# rect_and_stab.net
KiCad netlist of a schematic drawn in EAGLE
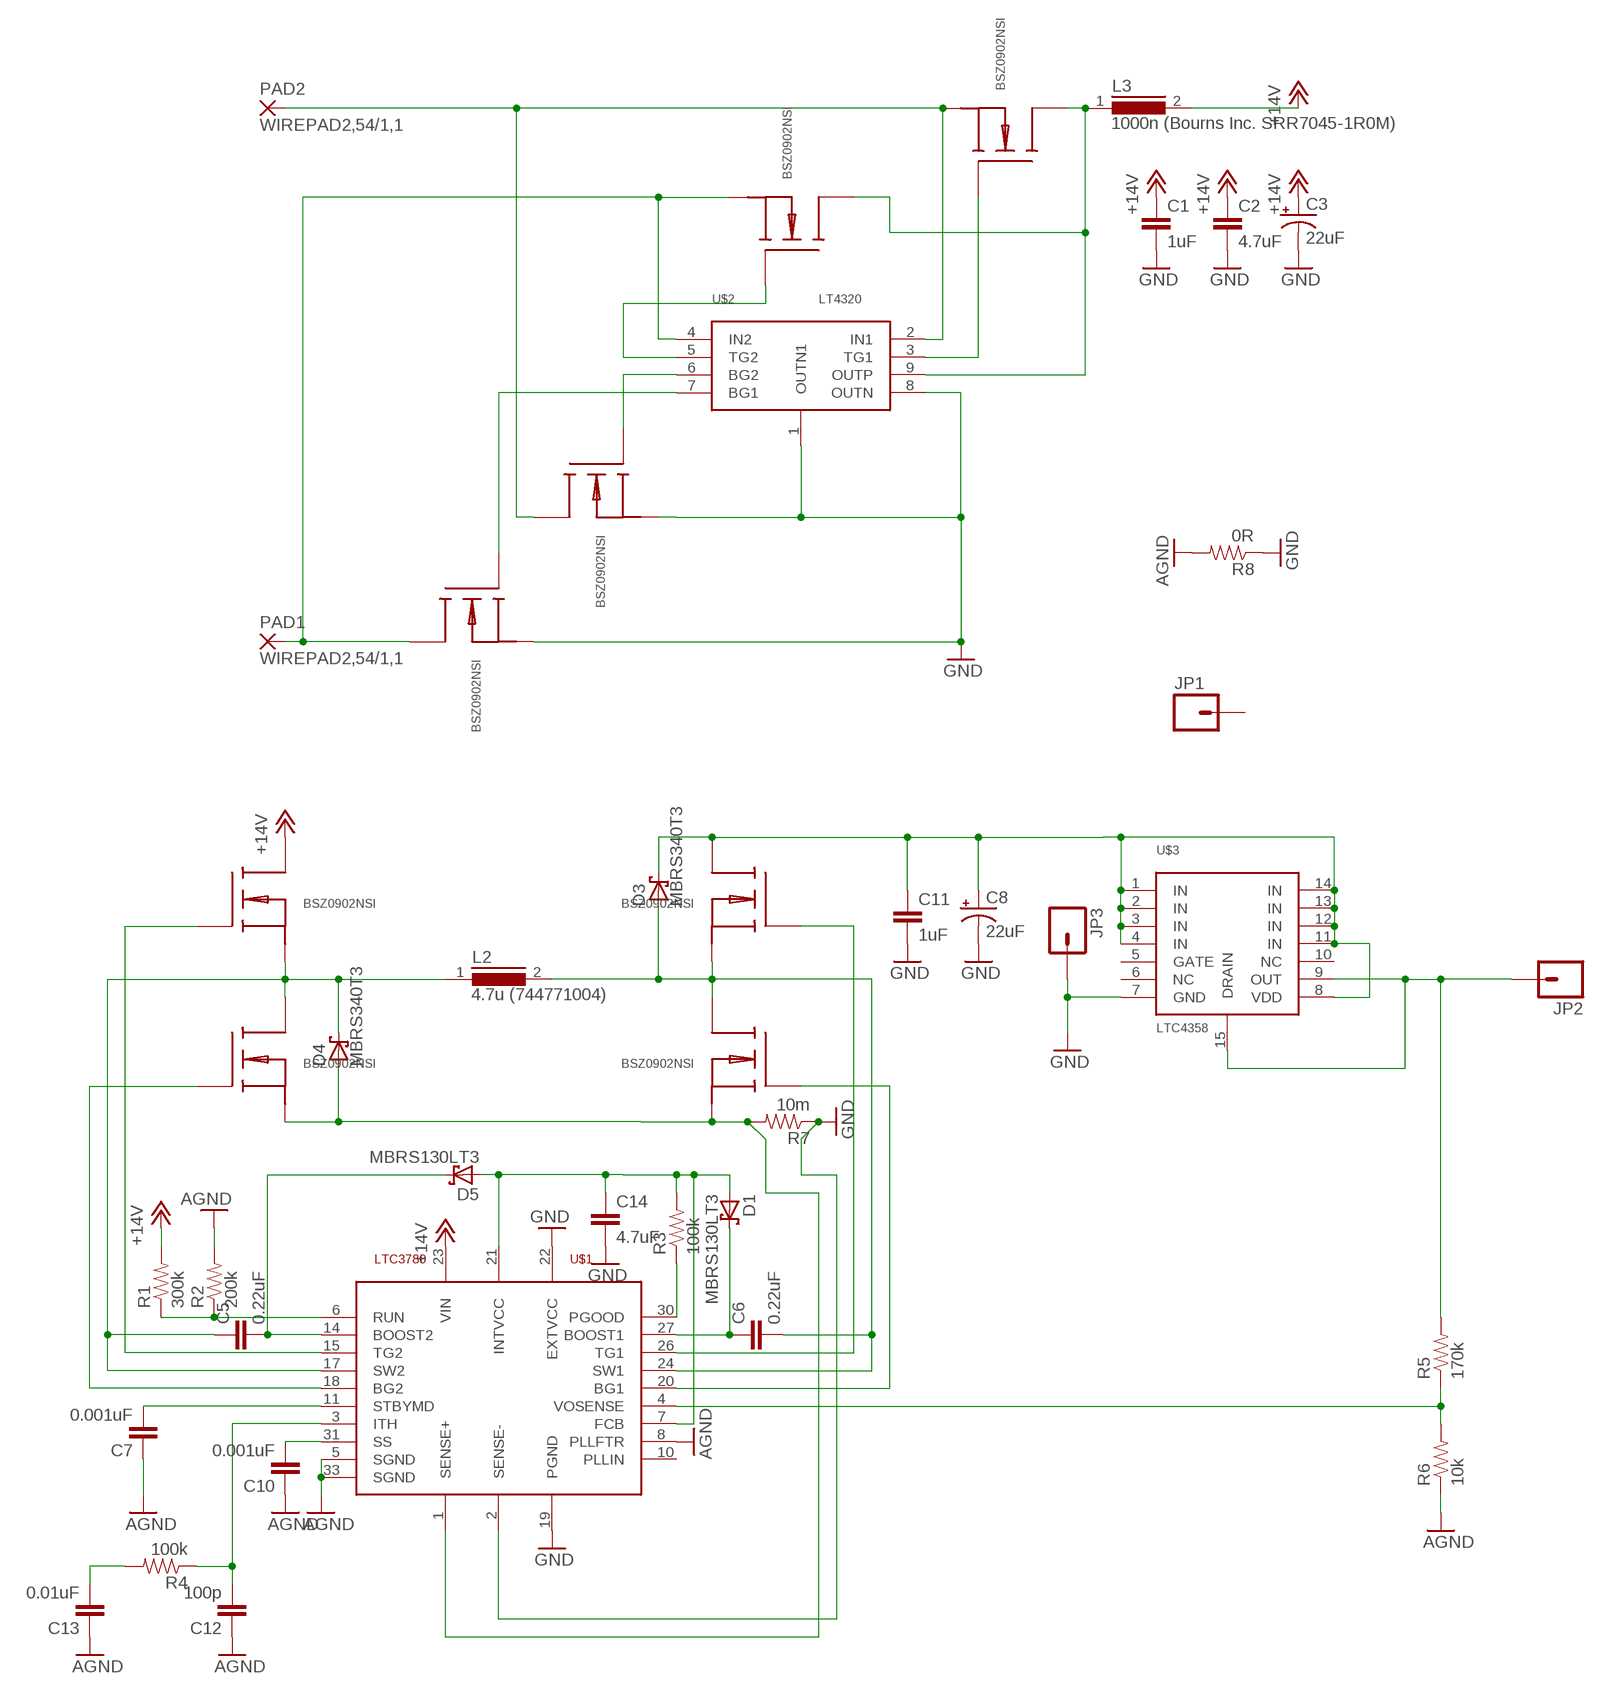
[diagram p0: schematic, sheet 1]

(export (version "E")
  (design (tool "Eeschema 10.0.6"))
  (components
    (comp (ref "C1")
      (value "1uF")
      (footprint "eagle-import:0603-CAP")
      (libsource (lib "eagle-import") (part "CAP0603-CAP"))
    )
    (comp (ref "C2")
      (value "4.7uF")
      (footprint "eagle-import:1210")
      (libsource (lib "eagle-import") (part "CAP1210"))
    )
    (comp (ref "C3")
      (value "22uF")
      (footprint "eagle-import:EIA7343")
      (libsource (lib "eagle-import") (part "CAP_POL7343"))
    )
    (comp (ref "C5")
      (value "0.22uF")
      (footprint "eagle-import:0603-CAP")
      (libsource (lib "eagle-import") (part "CAP0603-CAP"))
    )
    (comp (ref "C6")
      (value "0.22uF")
      (footprint "eagle-import:0603-CAP")
      (libsource (lib "eagle-import") (part "CAP0603-CAP"))
    )
    (comp (ref "C7")
      (value "0.001uF")
      (footprint "eagle-import:0402-CAP")
      (libsource (lib "eagle-import") (part "0.1UF-16V(+-10%)(0402)"))
    )
    (comp (ref "C8")
      (value "22uF")
      (footprint "eagle-import:EIA7343")
      (libsource (lib "eagle-import") (part "CAP_POL7343"))
    )
    (comp (ref "C10")
      (value "0.001uF")
      (footprint "eagle-import:0402-CAP")
      (libsource (lib "eagle-import") (part "0.1UF-16V(+-10%)(0402)"))
    )
    (comp (ref "C11")
      (value "1uF")
      (footprint "eagle-import:0603-CAP")
      (libsource (lib "eagle-import") (part "CAP0603-CAP"))
    )
    (comp (ref "C12")
      (value "100p")
      (footprint "eagle-import:0402-CAP")
      (libsource (lib "eagle-import") (part "0.1UF-16V(+-10%)(0402)"))
    )
    (comp (ref "C13")
      (value "0.01uF")
      (footprint "eagle-import:0402-CAP")
      (libsource (lib "eagle-import") (part "0.1UF-16V(+-10%)(0402)"))
    )
    (comp (ref "C14")
      (value "4.7uF")
      (footprint "eagle-import:1210")
      (libsource (lib "eagle-import") (part "CAP1210"))
    )
    (comp (ref "D1")
      (value "MBRS130LT3")
      (footprint "eagle-import:SMB")
      (libsource (lib "eagle-import") (part "MBRS130LT3"))
    )
    (comp (ref "D3")
      (value "MBRS340T3")
      (footprint "eagle-import:SMC")
      (libsource (lib "eagle-import") (part "MBRS30T34"))
    )
    (comp (ref "D4")
      (value "MBRS340T3")
      (footprint "eagle-import:SMC")
      (libsource (lib "eagle-import") (part "MBRS30T34"))
    )
    (comp (ref "D5")
      (value "MBRS130LT3")
      (footprint "eagle-import:SMB")
      (libsource (lib "eagle-import") (part "MBRS130LT3"))
    )
    (comp (ref "JP1")
      (value "M01PTH_2MM")
      (footprint "eagle-import:1X01_2MM")
      (libsource (lib "eagle-import") (part "M01PTH_2MM"))
    )
    (comp (ref "JP2")
      (value "M01PTH_2MM")
      (footprint "eagle-import:1X01_2MM")
      (libsource (lib "eagle-import") (part "M01PTH_2MM"))
    )
    (comp (ref "JP3")
      (value "M01PTH_2MM")
      (footprint "eagle-import:1X01_2MM")
      (libsource (lib "eagle-import") (part "M01PTH_2MM"))
    )
    (comp (ref "L2")
      (value "4.7u (744771004)")
      (footprint "eagle-import:DR127")
      (libsource (lib "eagle-import") (part "DR127"))
    )
    (comp (ref "L3")
      (value "1000n (Bourns Inc. SRR7045-1R0M)")
      (footprint "eagle-import:DR74")
      (libsource (lib "eagle-import") (part "DR74"))
    )
    (comp (ref "PAD1")
      (value "WIREPAD2,54/1,1")
      (footprint "eagle-import:2,54_1,1")
      (libsource (lib "eagle-import") (part "WIREPAD2,54/1,1"))
    )
    (comp (ref "PAD2")
      (value "WIREPAD2,54/1,1")
      (footprint "eagle-import:2,54_1,1")
      (libsource (lib "eagle-import") (part "WIREPAD2,54/1,1"))
    )
    (comp (ref "Q1")
      (value "BSZ0902NSI")
      (footprint "eagle-import:BSZ090X")
      (libsource (lib "eagle-import") (part "BSZ090X"))
    )
    (comp (ref "Q2")
      (value "BSZ0902NSI")
      (footprint "eagle-import:BSZ090X")
      (libsource (lib "eagle-import") (part "BSZ090X"))
    )
    (comp (ref "Q3")
      (value "BSZ0902NSI")
      (footprint "eagle-import:BSZ090X")
      (libsource (lib "eagle-import") (part "BSZ090X"))
    )
    (comp (ref "Q4")
      (value "BSZ0902NSI")
      (footprint "eagle-import:BSZ090X")
      (libsource (lib "eagle-import") (part "BSZ090X"))
    )
    (comp (ref "Q5")
      (value "BSZ0902NSI")
      (footprint "eagle-import:BSZ090X")
      (libsource (lib "eagle-import") (part "BSZ090X"))
    )
    (comp (ref "Q6")
      (value "BSZ0902NSI")
      (footprint "eagle-import:BSZ090X")
      (libsource (lib "eagle-import") (part "BSZ090X"))
    )
    (comp (ref "Q7")
      (value "BSZ0902NSI")
      (footprint "eagle-import:BSZ090X")
      (libsource (lib "eagle-import") (part "BSZ090X"))
    )
    (comp (ref "Q8")
      (value "BSZ0902NSI")
      (footprint "eagle-import:BSZ090X")
      (libsource (lib "eagle-import") (part "BSZ090X"))
    )
    (comp (ref "R1")
      (value "300k")
      (footprint "eagle-import:0402-RES")
      (libsource (lib "eagle-import") (part "RESISTOR0402-RES"))
    )
    (comp (ref "R2")
      (value "200k")
      (footprint "eagle-import:0402-RES")
      (libsource (lib "eagle-import") (part "RESISTOR0402-RES"))
    )
    (comp (ref "R3")
      (value "100k")
      (footprint "eagle-import:0402-RES")
      (libsource (lib "eagle-import") (part "RESISTOR0402-RES"))
    )
    (comp (ref "R4")
      (value "100k")
      (footprint "eagle-import:0402-RES")
      (libsource (lib "eagle-import") (part "RESISTOR0402-RES"))
    )
    (comp (ref "R5")
      (value "170k")
      (footprint "eagle-import:0402-RES")
      (libsource (lib "eagle-import") (part "RESISTOR0402-RES"))
    )
    (comp (ref "R6")
      (value "10k")
      (footprint "eagle-import:0402-RES")
      (libsource (lib "eagle-import") (part "RESISTOR0402-RES"))
    )
    (comp (ref "R7")
      (value "10m")
      (footprint "eagle-import:R2010")
      (libsource (lib "eagle-import") (part "RESISTOR2010"))
    )
    (comp (ref "R8")
      (value "0R")
      (footprint "eagle-import:0402-RES")
      (libsource (lib "eagle-import") (part "RESISTOR0402-RES"))
    )
    (comp (ref "U$1")
      (value "LTC3780")
      (footprint "eagle-import:LTC3780")
      (libsource (lib "eagle-import") (part "LTC3780"))
    )
    (comp (ref "U$2")
      (value "LT4320")
      (footprint "eagle-import:LT4320")
      (libsource (lib "eagle-import") (part "LT4320"))
    )
    (comp (ref "U$3")
      (value "LTC4358")
      (footprint "eagle-import:LTC4358")
      (libsource (lib "eagle-import") (part "LTC4358"))
    )
  )
  (nets
    (net (code "1") (name "+14V") (class "Default")
      (node (ref "C1") (pin "1") (pinfunction "1_1") (pintype "passive"))
      (node (ref "C2") (pin "1") (pinfunction "1_1") (pintype "passive"))
      (node (ref "C3") (pin "A") (pinfunction "+_A") (pintype "passive"))
      (node (ref "L3") (pin "2") (pinfunction "2_2") (pintype "passive"))
      (node (ref "Q6") (pin "D") (pinfunction "D_D") (pintype "bidirectional"))
      (node (ref "Q6") (pin "D@1") (pinfunction "D_D@1") (pintype "bidirectional"))
      (node (ref "Q6") (pin "D@2") (pinfunction "D_D@2") (pintype "bidirectional"))
      (node (ref "Q6") (pin "D@3") (pinfunction "D_D@3") (pintype "bidirectional"))
      (node (ref "Q6") (pin "D@4") (pinfunction "D_D@4") (pintype "bidirectional"))
      (node (ref "R1") (pin "2") (pinfunction "2_2") (pintype "passive"))
      (node (ref "U$1") (pin "23") (pinfunction "VIN_23") (pintype "power_in"))
    )
    (net (code "2") (name "AGND") (class "Default")
      (node (ref "C10") (pin "1") (pinfunction "1_1") (pintype "passive"))
      (node (ref "C12") (pin "1") (pinfunction "1_1") (pintype "passive"))
      (node (ref "C13") (pin "1") (pinfunction "1_1") (pintype "passive"))
      (node (ref "C7") (pin "1") (pinfunction "1_1") (pintype "passive"))
      (node (ref "R2") (pin "2") (pinfunction "2_2") (pintype "passive"))
      (node (ref "R6") (pin "1") (pinfunction "1_1") (pintype "passive"))
      (node (ref "R8") (pin "2") (pinfunction "2_2") (pintype "passive"))
      (node (ref "U$1") (pin "33") (pinfunction "SGND_33") (pintype "power_in"))
      (node (ref "U$1") (pin "5") (pinfunction "SGND_5") (pintype "power_in"))
      (node (ref "U$1") (pin "8") (pinfunction "PLLFTR_8") (pintype "bidirectional"))
    )
    (net (code "3") (name "GND") (class "Default")
      (node (ref "C1") (pin "2") (pinfunction "2_2") (pintype "passive"))
      (node (ref "C11") (pin "2") (pinfunction "2_2") (pintype "passive"))
      (node (ref "C14") (pin "2") (pinfunction "2_2") (pintype "passive"))
      (node (ref "C2") (pin "2") (pinfunction "2_2") (pintype "passive"))
      (node (ref "C3") (pin "C") (pinfunction "-_C") (pintype "passive"))
      (node (ref "C8") (pin "C") (pinfunction "-_C") (pintype "passive"))
      (node (ref "JP3") (pin "1") (pinfunction "1_1") (pintype "passive"))
      (node (ref "Q1") (pin "S@1") (pinfunction "S_S@1") (pintype "bidirectional"))
      (node (ref "Q1") (pin "S@2") (pinfunction "S_S@2") (pintype "bidirectional"))
      (node (ref "Q1") (pin "S@3") (pinfunction "S_S@3") (pintype "bidirectional"))
      (node (ref "Q1") (pin "S@4") (pinfunction "S_S@4") (pintype "bidirectional"))
      (node (ref "Q3") (pin "S@1") (pinfunction "S_S@1") (pintype "bidirectional"))
      (node (ref "Q3") (pin "S@2") (pinfunction "S_S@2") (pintype "bidirectional"))
      (node (ref "Q3") (pin "S@3") (pinfunction "S_S@3") (pintype "bidirectional"))
      (node (ref "Q3") (pin "S@4") (pinfunction "S_S@4") (pintype "bidirectional"))
      (node (ref "R7") (pin "1") (pinfunction "1_1") (pintype "passive"))
      (node (ref "R8") (pin "1") (pinfunction "1_1") (pintype "passive"))
      (node (ref "U$1") (pin "19") (pinfunction "PGND_19") (pintype "power_in"))
      (node (ref "U$1") (pin "2") (pinfunction "SENSE-_2") (pintype "bidirectional"))
      (node (ref "U$1") (pin "22") (pinfunction "EXTVCC_22") (pintype "bidirectional"))
      (node (ref "U$2") (pin "1") (pinfunction "OUTN1_1") (pintype "bidirectional"))
      (node (ref "U$2") (pin "8") (pinfunction "OUTN_8") (pintype "bidirectional"))
      (node (ref "U$3") (pin "7") (pinfunction "GND_7") (pintype "bidirectional"))
    )
    (net (code "4") (name "Net-(C8-+)") (class "Default")
      (node (ref "C11") (pin "1") (pinfunction "1_1") (pintype "passive"))
      (node (ref "C8") (pin "A") (pinfunction "+_A") (pintype "passive"))
      (node (ref "D3") (pin "C") (pinfunction "C_C") (pintype "passive"))
      (node (ref "Q8") (pin "D") (pinfunction "D_D") (pintype "bidirectional"))
      (node (ref "Q8") (pin "D@1") (pinfunction "D_D@1") (pintype "bidirectional"))
      (node (ref "Q8") (pin "D@2") (pinfunction "D_D@2") (pintype "bidirectional"))
      (node (ref "Q8") (pin "D@3") (pinfunction "D_D@3") (pintype "bidirectional"))
      (node (ref "Q8") (pin "D@4") (pinfunction "D_D@4") (pintype "bidirectional"))
      (node (ref "U$3") (pin "1") (pinfunction "IN_1") (pintype "bidirectional"))
      (node (ref "U$3") (pin "11") (pinfunction "IN_11") (pintype "bidirectional"))
      (node (ref "U$3") (pin "12") (pinfunction "IN_12") (pintype "bidirectional"))
      (node (ref "U$3") (pin "13") (pinfunction "IN_13") (pintype "bidirectional"))
      (node (ref "U$3") (pin "14") (pinfunction "IN_14") (pintype "bidirectional"))
      (node (ref "U$3") (pin "2") (pinfunction "IN_2") (pintype "bidirectional"))
      (node (ref "U$3") (pin "3") (pinfunction "IN_3") (pintype "bidirectional"))
      (node (ref "U$3") (pin "4") (pinfunction "IN_4") (pintype "bidirectional"))
      (node (ref "U$3") (pin "8") (pinfunction "VDD_8") (pintype "bidirectional"))
    )
    (net (code "5") (name "Net-(C13-Pad2)") (class "Default")
      (node (ref "C13") (pin "2") (pinfunction "2_2") (pintype "passive"))
      (node (ref "R4") (pin "2") (pinfunction "2_2") (pintype "passive"))
    )
    (net (code "6") (name "Net-(PAD1-P)") (class "Default")
      (node (ref "PAD1") (pin "1") (pinfunction "P_1") (pintype "passive"))
      (node (ref "Q2") (pin "S@1") (pinfunction "S_S@1") (pintype "bidirectional"))
      (node (ref "Q2") (pin "S@2") (pinfunction "S_S@2") (pintype "bidirectional"))
      (node (ref "Q2") (pin "S@3") (pinfunction "S_S@3") (pintype "bidirectional"))
      (node (ref "Q2") (pin "S@4") (pinfunction "S_S@4") (pintype "bidirectional"))
      (node (ref "Q3") (pin "D") (pinfunction "D_D") (pintype "bidirectional"))
      (node (ref "Q3") (pin "D@1") (pinfunction "D_D@1") (pintype "bidirectional"))
      (node (ref "Q3") (pin "D@2") (pinfunction "D_D@2") (pintype "bidirectional"))
      (node (ref "Q3") (pin "D@3") (pinfunction "D_D@3") (pintype "bidirectional"))
      (node (ref "Q3") (pin "D@4") (pinfunction "D_D@4") (pintype "bidirectional"))
      (node (ref "U$2") (pin "4") (pinfunction "IN2_4") (pintype "bidirectional"))
    )
    (net (code "7") (name "Net-(PAD2-P)") (class "Default")
      (node (ref "PAD2") (pin "1") (pinfunction "P_1") (pintype "passive"))
      (node (ref "Q1") (pin "D") (pinfunction "D_D") (pintype "bidirectional"))
      (node (ref "Q1") (pin "D@1") (pinfunction "D_D@1") (pintype "bidirectional"))
      (node (ref "Q1") (pin "D@2") (pinfunction "D_D@2") (pintype "bidirectional"))
      (node (ref "Q1") (pin "D@3") (pinfunction "D_D@3") (pintype "bidirectional"))
      (node (ref "Q1") (pin "D@4") (pinfunction "D_D@4") (pintype "bidirectional"))
      (node (ref "Q4") (pin "S@1") (pinfunction "S_S@1") (pintype "bidirectional"))
      (node (ref "Q4") (pin "S@2") (pinfunction "S_S@2") (pintype "bidirectional"))
      (node (ref "Q4") (pin "S@3") (pinfunction "S_S@3") (pintype "bidirectional"))
      (node (ref "Q4") (pin "S@4") (pinfunction "S_S@4") (pintype "bidirectional"))
      (node (ref "U$2") (pin "2") (pinfunction "IN1_2") (pintype "bidirectional"))
    )
    (net (code "8") (name "Net-(U$1-BG1)") (class "Default")
      (node (ref "Q7") (pin "G") (pinfunction "G_G") (pintype "bidirectional"))
      (node (ref "U$1") (pin "20") (pinfunction "BG1_20") (pintype "bidirectional"))
    )
    (net (code "9") (name "Net-(U$1-BG2)") (class "Default")
      (node (ref "Q5") (pin "G") (pinfunction "G_G") (pintype "bidirectional"))
      (node (ref "U$1") (pin "18") (pinfunction "BG2_18") (pintype "bidirectional"))
    )
    (net (code "10") (name "Net-(U$1-BOOST1)") (class "Default")
      (node (ref "C6") (pin "1") (pinfunction "1_1") (pintype "passive"))
      (node (ref "D1") (pin "C") (pinfunction "C_C") (pintype "passive"))
      (node (ref "U$1") (pin "27") (pinfunction "BOOST1_27") (pintype "bidirectional"))
    )
    (net (code "11") (name "Net-(U$1-BOOST2)") (class "Default")
      (node (ref "C5") (pin "2") (pinfunction "2_2") (pintype "passive"))
      (node (ref "D5") (pin "C") (pinfunction "C_C") (pintype "passive"))
      (node (ref "U$1") (pin "14") (pinfunction "BOOST2_14") (pintype "bidirectional"))
    )
    (net (code "12") (name "Net-(U$1-FCB)") (class "Default")
      (node (ref "C14") (pin "1") (pinfunction "1_1") (pintype "passive"))
      (node (ref "D1") (pin "A") (pinfunction "A_A") (pintype "passive"))
      (node (ref "D5") (pin "A") (pinfunction "A_A") (pintype "passive"))
      (node (ref "R3") (pin "2") (pinfunction "2_2") (pintype "passive"))
      (node (ref "U$1") (pin "21") (pinfunction "INTVCC_21") (pintype "bidirectional"))
      (node (ref "U$1") (pin "7") (pinfunction "FCB_7") (pintype "bidirectional"))
    )
    (net (code "13") (name "Net-(U$1-ITH)") (class "Default")
      (node (ref "C12") (pin "2") (pinfunction "2_2") (pintype "passive"))
      (node (ref "R4") (pin "1") (pinfunction "1_1") (pintype "passive"))
      (node (ref "U$1") (pin "3") (pinfunction "ITH_3") (pintype "bidirectional"))
    )
    (net (code "14") (name "Net-(U$1-PGOOD)") (class "Default")
      (node (ref "R3") (pin "1") (pinfunction "1_1") (pintype "passive"))
      (node (ref "U$1") (pin "30") (pinfunction "PGOOD_30") (pintype "bidirectional"))
    )
    (net (code "15") (name "Net-(U$1-RUN)") (class "Default")
      (node (ref "R1") (pin "1") (pinfunction "1_1") (pintype "passive"))
      (node (ref "R2") (pin "1") (pinfunction "1_1") (pintype "passive"))
      (node (ref "U$1") (pin "6") (pinfunction "RUN_6") (pintype "bidirectional"))
    )
    (net (code "16") (name "Net-(U$1-SENSE+)") (class "Default")
      (node (ref "D4") (pin "A") (pinfunction "A_A") (pintype "passive"))
      (node (ref "Q5") (pin "S@1") (pinfunction "S_S@1") (pintype "bidirectional"))
      (node (ref "Q5") (pin "S@2") (pinfunction "S_S@2") (pintype "bidirectional"))
      (node (ref "Q5") (pin "S@3") (pinfunction "S_S@3") (pintype "bidirectional"))
      (node (ref "Q5") (pin "S@4") (pinfunction "S_S@4") (pintype "bidirectional"))
      (node (ref "Q7") (pin "S@1") (pinfunction "S_S@1") (pintype "bidirectional"))
      (node (ref "Q7") (pin "S@2") (pinfunction "S_S@2") (pintype "bidirectional"))
      (node (ref "Q7") (pin "S@3") (pinfunction "S_S@3") (pintype "bidirectional"))
      (node (ref "Q7") (pin "S@4") (pinfunction "S_S@4") (pintype "bidirectional"))
      (node (ref "R7") (pin "2") (pinfunction "2_2") (pintype "passive"))
      (node (ref "U$1") (pin "1") (pinfunction "SENSE+_1") (pintype "bidirectional"))
    )
    (net (code "17") (name "Net-(U$1-SS)") (class "Default")
      (node (ref "C10") (pin "2") (pinfunction "2_2") (pintype "passive"))
      (node (ref "U$1") (pin "31") (pinfunction "SS_31") (pintype "bidirectional"))
    )
    (net (code "18") (name "Net-(U$1-STBYMD)") (class "Default")
      (node (ref "C7") (pin "2") (pinfunction "2_2") (pintype "passive"))
      (node (ref "U$1") (pin "11") (pinfunction "STBYMD_11") (pintype "bidirectional"))
    )
    (net (code "19") (name "Net-(U$1-SW1)") (class "Default")
      (node (ref "C6") (pin "2") (pinfunction "2_2") (pintype "passive"))
      (node (ref "D3") (pin "A") (pinfunction "A_A") (pintype "passive"))
      (node (ref "L2") (pin "2") (pinfunction "2_2") (pintype "passive"))
      (node (ref "Q7") (pin "D") (pinfunction "D_D") (pintype "bidirectional"))
      (node (ref "Q7") (pin "D@1") (pinfunction "D_D@1") (pintype "bidirectional"))
      (node (ref "Q7") (pin "D@2") (pinfunction "D_D@2") (pintype "bidirectional"))
      (node (ref "Q7") (pin "D@3") (pinfunction "D_D@3") (pintype "bidirectional"))
      (node (ref "Q7") (pin "D@4") (pinfunction "D_D@4") (pintype "bidirectional"))
      (node (ref "Q8") (pin "S@1") (pinfunction "S_S@1") (pintype "bidirectional"))
      (node (ref "Q8") (pin "S@2") (pinfunction "S_S@2") (pintype "bidirectional"))
      (node (ref "Q8") (pin "S@3") (pinfunction "S_S@3") (pintype "bidirectional"))
      (node (ref "Q8") (pin "S@4") (pinfunction "S_S@4") (pintype "bidirectional"))
      (node (ref "U$1") (pin "24") (pinfunction "SW1_24") (pintype "bidirectional"))
    )
    (net (code "20") (name "Net-(U$1-SW2)") (class "Default")
      (node (ref "C5") (pin "1") (pinfunction "1_1") (pintype "passive"))
      (node (ref "D4") (pin "C") (pinfunction "C_C") (pintype "passive"))
      (node (ref "L2") (pin "1") (pinfunction "1_1") (pintype "passive"))
      (node (ref "Q5") (pin "D") (pinfunction "D_D") (pintype "bidirectional"))
      (node (ref "Q5") (pin "D@1") (pinfunction "D_D@1") (pintype "bidirectional"))
      (node (ref "Q5") (pin "D@2") (pinfunction "D_D@2") (pintype "bidirectional"))
      (node (ref "Q5") (pin "D@3") (pinfunction "D_D@3") (pintype "bidirectional"))
      (node (ref "Q5") (pin "D@4") (pinfunction "D_D@4") (pintype "bidirectional"))
      (node (ref "Q6") (pin "S@1") (pinfunction "S_S@1") (pintype "bidirectional"))
      (node (ref "Q6") (pin "S@2") (pinfunction "S_S@2") (pintype "bidirectional"))
      (node (ref "Q6") (pin "S@3") (pinfunction "S_S@3") (pintype "bidirectional"))
      (node (ref "Q6") (pin "S@4") (pinfunction "S_S@4") (pintype "bidirectional"))
      (node (ref "U$1") (pin "17") (pinfunction "SW2_17") (pintype "bidirectional"))
    )
    (net (code "21") (name "Net-(U$1-TG1)") (class "Default")
      (node (ref "Q8") (pin "G") (pinfunction "G_G") (pintype "bidirectional"))
      (node (ref "U$1") (pin "26") (pinfunction "TG1_26") (pintype "bidirectional"))
    )
    (net (code "22") (name "Net-(U$1-TG2)") (class "Default")
      (node (ref "Q6") (pin "G") (pinfunction "G_G") (pintype "bidirectional"))
      (node (ref "U$1") (pin "15") (pinfunction "TG2_15") (pintype "bidirectional"))
    )
    (net (code "23") (name "Net-(U$1-VOSENSE)") (class "Default")
      (node (ref "R5") (pin "1") (pinfunction "1_1") (pintype "passive"))
      (node (ref "R6") (pin "2") (pinfunction "2_2") (pintype "passive"))
      (node (ref "U$1") (pin "4") (pinfunction "VOSENSE_4") (pintype "bidirectional"))
    )
    (net (code "24") (name "Net-(U$2-BG1)") (class "Default")
      (node (ref "Q3") (pin "G") (pinfunction "G_G") (pintype "bidirectional"))
      (node (ref "U$2") (pin "7") (pinfunction "BG1_7") (pintype "bidirectional"))
    )
    (net (code "25") (name "Net-(U$2-BG2)") (class "Default")
      (node (ref "Q1") (pin "G") (pinfunction "G_G") (pintype "bidirectional"))
      (node (ref "U$2") (pin "6") (pinfunction "BG2_6") (pintype "bidirectional"))
    )
    (net (code "26") (name "Net-(U$2-OUTP)") (class "Default")
      (node (ref "L3") (pin "1") (pinfunction "1_1") (pintype "passive"))
      (node (ref "Q2") (pin "D") (pinfunction "D_D") (pintype "bidirectional"))
      (node (ref "Q2") (pin "D@1") (pinfunction "D_D@1") (pintype "bidirectional"))
      (node (ref "Q2") (pin "D@2") (pinfunction "D_D@2") (pintype "bidirectional"))
      (node (ref "Q2") (pin "D@3") (pinfunction "D_D@3") (pintype "bidirectional"))
      (node (ref "Q2") (pin "D@4") (pinfunction "D_D@4") (pintype "bidirectional"))
      (node (ref "Q4") (pin "D") (pinfunction "D_D") (pintype "bidirectional"))
      (node (ref "Q4") (pin "D@1") (pinfunction "D_D@1") (pintype "bidirectional"))
      (node (ref "Q4") (pin "D@2") (pinfunction "D_D@2") (pintype "bidirectional"))
      (node (ref "Q4") (pin "D@3") (pinfunction "D_D@3") (pintype "bidirectional"))
      (node (ref "Q4") (pin "D@4") (pinfunction "D_D@4") (pintype "bidirectional"))
      (node (ref "U$2") (pin "9") (pinfunction "OUTP_9") (pintype "bidirectional"))
    )
    (net (code "27") (name "Net-(U$2-TG1)") (class "Default")
      (node (ref "Q4") (pin "G") (pinfunction "G_G") (pintype "bidirectional"))
      (node (ref "U$2") (pin "3") (pinfunction "TG1_3") (pintype "bidirectional"))
    )
    (net (code "28") (name "Net-(U$2-TG2)") (class "Default")
      (node (ref "Q2") (pin "G") (pinfunction "G_G") (pintype "bidirectional"))
      (node (ref "U$2") (pin "5") (pinfunction "TG2_5") (pintype "bidirectional"))
    )
    (net (code "29") (name "Net-(U$3-DRAIN)") (class "Default")
      (node (ref "JP2") (pin "1") (pinfunction "1_1") (pintype "passive"))
      (node (ref "R5") (pin "2") (pinfunction "2_2") (pintype "passive"))
      (node (ref "U$3") (pin "15") (pinfunction "DRAIN_15") (pintype "bidirectional"))
      (node (ref "U$3") (pin "9") (pinfunction "OUT_9") (pintype "bidirectional"))
    )
    (net (code "30") (name "unconnected-(JP1-Pad1)") (class "Default")
      (node (ref "JP1") (pin "1") (pinfunction "1_1") (pintype "passive"))
    )
    (net (code "31") (name "unconnected-(U$1-NC-Pad9)") (class "Default")
      (node (ref "U$1") (pin "9") (pinfunction "NC_9") (pintype "no_connect"))
    )
    (net (code "32") (name "unconnected-(U$1-NC-Pad12)") (class "Default")
      (node (ref "U$1") (pin "12") (pinfunction "NC_12") (pintype "no_connect"))
    )
    (net (code "33") (name "unconnected-(U$1-NC-Pad13)") (class "Default")
      (node (ref "U$1") (pin "13") (pinfunction "NC_13") (pintype "no_connect"))
    )
    (net (code "34") (name "unconnected-(U$1-NC-Pad16)") (class "Default")
      (node (ref "U$1") (pin "16") (pinfunction "NC_16") (pintype "no_connect"))
    )
    (net (code "35") (name "unconnected-(U$1-NC-Pad25)") (class "Default")
      (node (ref "U$1") (pin "25") (pinfunction "NC_25") (pintype "no_connect"))
    )
    (net (code "36") (name "unconnected-(U$1-NC-Pad28)") (class "Default")
      (node (ref "U$1") (pin "28") (pinfunction "NC_28") (pintype "no_connect"))
    )
    (net (code "37") (name "unconnected-(U$1-NC-Pad29)") (class "Default")
      (node (ref "U$1") (pin "29") (pinfunction "NC_29") (pintype "no_connect"))
    )
    (net (code "38") (name "unconnected-(U$1-NC-Pad32)") (class "Default")
      (node (ref "U$1") (pin "32") (pinfunction "NC_32") (pintype "no_connect"))
    )
    (net (code "39") (name "unconnected-(U$1-PLLIN-Pad10)") (class "Default")
      (node (ref "U$1") (pin "10") (pinfunction "PLLIN_10") (pintype "bidirectional"))
    )
    (net (code "40") (name "unconnected-(U$3-GATE-Pad5)") (class "Default")
      (node (ref "U$3") (pin "5") (pinfunction "GATE_5") (pintype "bidirectional"))
    )
    (net (code "41") (name "unconnected-(U$3-NC-Pad6)") (class "Default")
      (node (ref "U$3") (pin "6") (pinfunction "NC_6") (pintype "bidirectional"))
    )
    (net (code "42") (name "unconnected-(U$3-NC-Pad10)") (class "Default")
      (node (ref "U$3") (pin "10") (pinfunction "NC_10") (pintype "bidirectional"))
    )
  )
)
